# FPVCaptureTheFlag.net
KiCad netlist of a schematic drawn in EAGLE
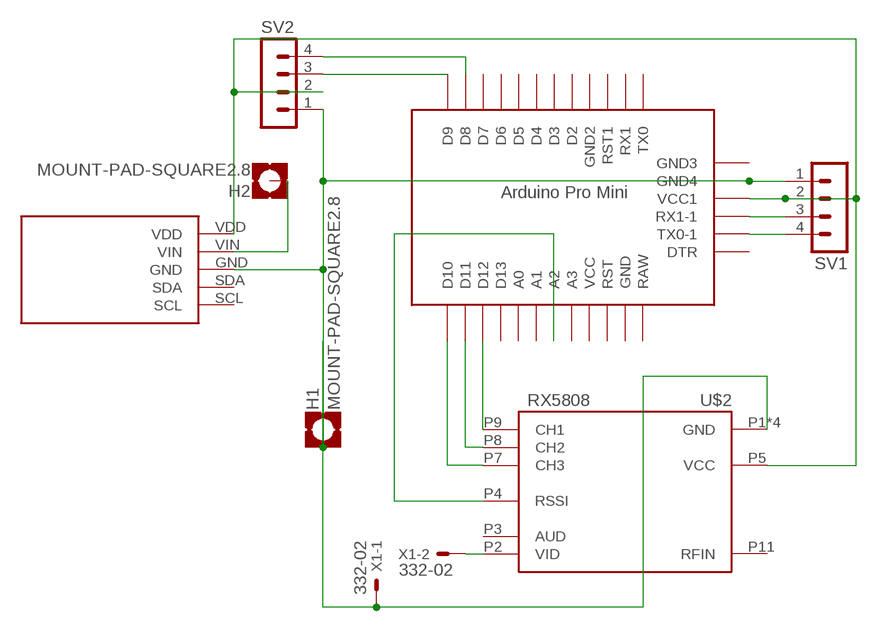
[diagram p0: schematic, sheet 1]

(export (version "E")
  (design (tool "Eeschema 10.0.6"))
  (components
    (comp (ref "H1")
      (value "MOUNT-PAD-SQUARE2.8")
      (footprint "eagle-import:2,8-PAD-SQUARE")
      (libsource (lib "eagle-import") (part "MOUNT-PAD-SQUARE2.8"))
    )
    (comp (ref "H2")
      (value "MOUNT-PAD-SQUARE2.8")
      (footprint "eagle-import:2,8-PAD-SQUARE")
      (libsource (lib "eagle-import") (part "MOUNT-PAD-SQUARE2.8"))
    )
    (comp (ref "SV1")
      (value "MA04-1")
      (footprint "eagle-import:MA04-1")
      (libsource (lib "eagle-import") (part "MA04-1"))
    )
    (comp (ref "SV2")
      (value "MA04-1")
      (footprint "eagle-import:MA04-1")
      (libsource (lib "eagle-import") (part "MA04-1"))
    )
    (comp (ref "U$1")
      (value "ABK-PRO-MINI")
      (footprint "eagle-import:ABK-PRO-MINI")
      (libsource (lib "eagle-import") (part "ABK-PRO-MINI"))
    )
    (comp (ref "U$2")
      (value "RX5808")
      (footprint "eagle-import:RX5808")
      (libsource (lib "eagle-import") (part "RX5808"))
    )
    (comp (ref "U$3")
      (value "POLOLU_MINIMU9_V2THROUGHHOLE")
      (footprint "eagle-import:POLOLU_MINIMU9_V2")
      (libsource (lib "eagle-import") (part "POLOLU_MINIMU9_V2THROUGHHOLE"))
    )
    (comp (ref "X1")
      (value "332-02")
      (footprint "eagle-import:332-02")
      (libsource (lib "eagle-import") (part "332-02"))
    )
  )
  (nets
    (net (code "1") (name "Net-(H1-MOUNT)") (class "Default")
      (node (ref "H1") (pin "B2,8") (pinfunction "MOUNT_B2,8") (pintype "passive"))
      (node (ref "SV1") (pin "1") (pinfunction "1_1") (pintype "passive"))
      (node (ref "SV2") (pin "1") (pinfunction "1_1") (pintype "passive"))
      (node (ref "U$1") (pin "GND3") (pinfunction "GND4_GND3") (pintype "bidirectional"))
      (node (ref "U$2") (pin "P1") (pinfunction "GND_P1") (pintype "bidirectional"))
      (node (ref "U$2") (pin "P10") (pinfunction "GND_P10") (pintype "bidirectional"))
      (node (ref "U$2") (pin "P12") (pinfunction "GND_P12") (pintype "bidirectional"))
      (node (ref "U$2") (pin "P6") (pinfunction "GND_P6") (pintype "bidirectional"))
      (node (ref "U$3") (pin "GND") (pinfunction "GND_GND") (pintype "bidirectional"))
      (node (ref "X1") (pin "1") (pinfunction "S_1") (pintype "passive"))
    )
    (net (code "2") (name "Net-(H2-MOUNT)") (class "Default")
      (node (ref "H2") (pin "B2,8") (pinfunction "MOUNT_B2,8") (pintype "passive"))
      (node (ref "U$3") (pin "VIN") (pinfunction "VIN_VIN") (pintype "bidirectional"))
    )
    (net (code "3") (name "Net-(SV1-Pad3)") (class "Default")
      (node (ref "SV1") (pin "3") (pinfunction "3_3") (pintype "passive"))
      (node (ref "U$1") (pin "RX1-1") (pinfunction "RX1-1_RX1-1") (pintype "bidirectional"))
    )
    (net (code "4") (name "Net-(SV1-Pad4)") (class "Default")
      (node (ref "SV1") (pin "4") (pinfunction "4_4") (pintype "passive"))
      (node (ref "U$1") (pin "TX0-1") (pinfunction "TX0-1_TX0-1") (pintype "bidirectional"))
    )
    (net (code "5") (name "Net-(SV2-Pad3)") (class "Default")
      (node (ref "SV2") (pin "3") (pinfunction "3_3") (pintype "passive"))
      (node (ref "U$1") (pin "D9") (pinfunction "D9_D9") (pintype "bidirectional"))
    )
    (net (code "6") (name "Net-(SV2-Pad4)") (class "Default")
      (node (ref "SV2") (pin "4") (pinfunction "4_4") (pintype "passive"))
      (node (ref "U$1") (pin "D8") (pinfunction "D8_D8") (pintype "bidirectional"))
    )
    (net (code "7") (name "Net-(U$2-CH1)") (class "Default")
      (node (ref "U$1") (pin "D12") (pinfunction "D12_D12") (pintype "bidirectional"))
      (node (ref "U$2") (pin "P9") (pinfunction "CH1_P9") (pintype "bidirectional"))
    )
    (net (code "8") (name "Net-(U$2-CH2)") (class "Default")
      (node (ref "U$1") (pin "D11") (pinfunction "D11_D11") (pintype "bidirectional"))
      (node (ref "U$2") (pin "P8") (pinfunction "CH2_P8") (pintype "bidirectional"))
    )
    (net (code "9") (name "Net-(U$2-CH3)") (class "Default")
      (node (ref "U$1") (pin "D10") (pinfunction "D10_D10") (pintype "bidirectional"))
      (node (ref "U$2") (pin "P7") (pinfunction "CH3_P7") (pintype "bidirectional"))
    )
    (net (code "10") (name "Net-(U$2-RSSI)") (class "Default")
      (node (ref "U$1") (pin "A2") (pinfunction "A2_A2") (pintype "bidirectional"))
      (node (ref "U$2") (pin "P4") (pinfunction "RSSI_P4") (pintype "bidirectional"))
    )
    (net (code "11") (name "Net-(U$2-VCC)") (class "Default")
      (node (ref "SV1") (pin "2") (pinfunction "2_2") (pintype "passive"))
      (node (ref "SV2") (pin "2") (pinfunction "2_2") (pintype "passive"))
      (node (ref "U$1") (pin "VCC1") (pinfunction "VCC1_VCC1") (pintype "bidirectional"))
      (node (ref "U$2") (pin "P5") (pinfunction "VCC_P5") (pintype "bidirectional"))
      (node (ref "U$3") (pin "VDD") (pinfunction "VDD_VDD") (pintype "bidirectional"))
    )
    (net (code "12") (name "Net-(U$2-VID)") (class "Default")
      (node (ref "U$2") (pin "P2") (pinfunction "VID_P2") (pintype "bidirectional"))
      (node (ref "X1") (pin "2") (pinfunction "S_2") (pintype "passive"))
    )
    (net (code "13") (name "unconnected-(U$1-GND2-PadGND1)") (class "Default")
      (node (ref "U$1") (pin "GND1") (pinfunction "GND2_GND1") (pintype "bidirectional"))
    )
    (net (code "14") (name "unconnected-(U$1-GND3-PadGND2)") (class "Default")
      (node (ref "U$1") (pin "GND2") (pinfunction "GND3_GND2") (pintype "bidirectional"))
    )
    (net (code "15") (name "unconnected-(U$1-PadA0)") (class "Default")
      (node (ref "U$1") (pin "A0") (pinfunction "A0_A0") (pintype "bidirectional"))
    )
    (net (code "16") (name "unconnected-(U$1-PadA1)") (class "Default")
      (node (ref "U$1") (pin "A1") (pinfunction "A1_A1") (pintype "bidirectional"))
    )
    (net (code "17") (name "unconnected-(U$1-PadA3)") (class "Default")
      (node (ref "U$1") (pin "A3") (pinfunction "A3_A3") (pintype "bidirectional"))
    )
    (net (code "18") (name "unconnected-(U$1-PadD2)") (class "Default")
      (node (ref "U$1") (pin "D2") (pinfunction "D2_D2") (pintype "bidirectional"))
    )
    (net (code "19") (name "unconnected-(U$1-PadD3)") (class "Default")
      (node (ref "U$1") (pin "D3") (pinfunction "D3_D3") (pintype "bidirectional"))
    )
    (net (code "20") (name "unconnected-(U$1-PadD4)") (class "Default")
      (node (ref "U$1") (pin "D4") (pinfunction "D4_D4") (pintype "bidirectional"))
    )
    (net (code "21") (name "unconnected-(U$1-PadD5)") (class "Default")
      (node (ref "U$1") (pin "D5") (pinfunction "D5_D5") (pintype "bidirectional"))
    )
    (net (code "22") (name "unconnected-(U$1-PadD6)") (class "Default")
      (node (ref "U$1") (pin "D6") (pinfunction "D6_D6") (pintype "bidirectional"))
    )
    (net (code "23") (name "unconnected-(U$1-PadD7)") (class "Default")
      (node (ref "U$1") (pin "D7") (pinfunction "D7_D7") (pintype "bidirectional"))
    )
    (net (code "24") (name "unconnected-(U$1-PadD13)") (class "Default")
      (node (ref "U$1") (pin "D13") (pinfunction "D13_D13") (pintype "bidirectional"))
    )
    (net (code "25") (name "unconnected-(U$1-PadDTR)") (class "Default")
      (node (ref "U$1") (pin "DTR") (pinfunction "DTR_DTR") (pintype "bidirectional"))
    )
    (net (code "26") (name "unconnected-(U$1-PadGND)") (class "Default")
      (node (ref "U$1") (pin "GND") (pinfunction "GND_GND") (pintype "bidirectional"))
    )
    (net (code "27") (name "unconnected-(U$1-PadRAW)") (class "Default")
      (node (ref "U$1") (pin "RAW") (pinfunction "RAW_RAW") (pintype "bidirectional"))
    )
    (net (code "28") (name "unconnected-(U$1-PadRST)") (class "Default")
      (node (ref "U$1") (pin "RST") (pinfunction "RST_RST") (pintype "bidirectional"))
    )
    (net (code "29") (name "unconnected-(U$1-PadRST1)") (class "Default")
      (node (ref "U$1") (pin "RST1") (pinfunction "RST1_RST1") (pintype "bidirectional"))
    )
    (net (code "30") (name "unconnected-(U$1-PadRX1)") (class "Default")
      (node (ref "U$1") (pin "RX1") (pinfunction "RX1_RX1") (pintype "bidirectional"))
    )
    (net (code "31") (name "unconnected-(U$1-PadTX0)") (class "Default")
      (node (ref "U$1") (pin "TX0") (pinfunction "TX0_TX0") (pintype "bidirectional"))
    )
    (net (code "32") (name "unconnected-(U$1-PadVCC)") (class "Default")
      (node (ref "U$1") (pin "VCC") (pinfunction "VCC_VCC") (pintype "bidirectional"))
    )
    (net (code "33") (name "unconnected-(U$2-AUD-PadP3)") (class "Default")
      (node (ref "U$2") (pin "P3") (pinfunction "AUD_P3") (pintype "bidirectional"))
    )
    (net (code "34") (name "unconnected-(U$2-RFIN-PadP11)") (class "Default")
      (node (ref "U$2") (pin "P11") (pinfunction "RFIN_P11") (pintype "bidirectional"))
    )
    (net (code "35") (name "unconnected-(U$3-PadSCL)") (class "Default")
      (node (ref "U$3") (pin "SCL") (pinfunction "SCL_SCL") (pintype "bidirectional"))
    )
    (net (code "36") (name "unconnected-(U$3-PadSDA)") (class "Default")
      (node (ref "U$3") (pin "SDA") (pinfunction "SDA_SDA") (pintype "bidirectional"))
    )
  )
)
